# 2_ADSTM32-MCU.net
KiCad netlist of a schematic drawn in Altium Designer
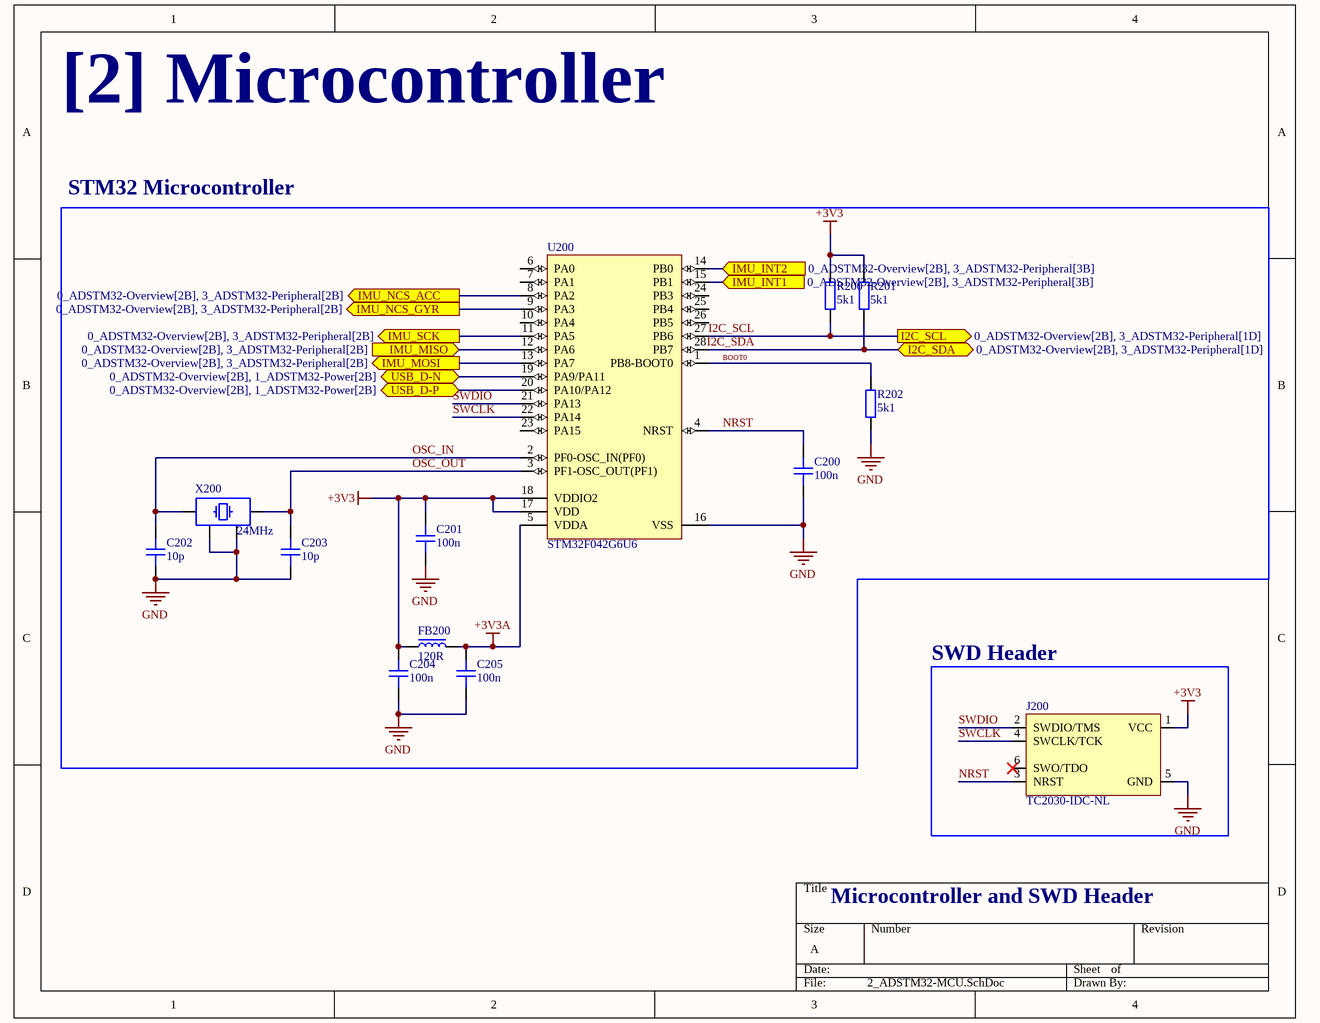
[diagram p0:  2_ADSTM32-MCU.SchDoc]

(export (version "E")
  (design (tool "Eeschema 10.0.6"))
  (components
    (comp (ref "C200")
      (value "100n")
      (footprint "CAP_0603")
      (description "Capaictor SMD 0603 Generic")
      (libsource (lib "Schematic-Lib-KEM") (part "CAP_0603"))
    )
    (comp (ref "C201")
      (value "100n")
      (footprint "CAP_0603")
      (description "Capaictor SMD 0603 Generic")
      (libsource (lib "Schematic-Lib-KEM") (part "CAP_0603"))
    )
    (comp (ref "C202")
      (value "10p")
      (footprint "CAP_0603")
      (description "Capaictor SMD 0603 Generic")
      (libsource (lib "Schematic-Lib-KEM") (part "CAP_0603"))
    )
    (comp (ref "C203")
      (value "10p")
      (footprint "CAP_0603")
      (description "Capaictor SMD 0603 Generic")
      (libsource (lib "Schematic-Lib-KEM") (part "CAP_0603"))
    )
    (comp (ref "C204")
      (value "100n")
      (footprint "CAP_0603")
      (description "Capaictor SMD 0603 Generic")
      (libsource (lib "Schematic-Lib-KEM") (part "CAP_0603"))
    )
    (comp (ref "C205")
      (value "100n")
      (footprint "CAP_0603")
      (description "Capaictor SMD 0603 Generic")
      (libsource (lib "Schematic-Lib-KEM") (part "CAP_0603"))
    )
    (comp (ref "FB200")
      (value "120R")
      (footprint "FB_0603")
      (description "Ferrite Beads BMC-Q 0603 120R 25% Tol. High Current")
      (fields
        (field (name "MANUFACTURER") "Bourns")
        (field (name "MANUFACTURER PART NUMBER") "BMC-Q1JY0120H")
      )
      (libsource (lib "Schematic-Lib-KEM") (part "BMC-Q1JY0120H"))
    )
    (comp (ref "J200")
      (value "TC2030-IDC-NL")
      (footprint "TC2030_NL")
      (description "Tag-Connect No-Solder SWD Debug Connector (No Legs)")
      (libsource (lib "Schematic-Lib-KEM") (part "TC2030-IDC-NL"))
    )
    (comp (ref "R200")
      (value "5k1")
      (footprint "RES_0603")
      (description "Resistor SMD 0603 Generic")
      (libsource (lib "Schematic-Lib-KEM") (part "RES_0603"))
    )
    (comp (ref "R201")
      (value "5k1")
      (footprint "RES_0603")
      (description "Resistor SMD 0603 Generic")
      (libsource (lib "Schematic-Lib-KEM") (part "RES_0603"))
    )
    (comp (ref "R202")
      (value "5k1")
      (footprint "RES_0603")
      (description "Resistor SMD 0603 Generic")
      (libsource (lib "Schematic-Lib-KEM") (part "RES_0603"))
    )
    (comp (ref "U200")
      (value "STM32F042G6U6")
      (footprint "STM-UFQFPN28_V")
      (fields (field (name "MANUFACTURER") "STMicroelectronics"))
      (libsource (lib "Altium Content Vault") (part "MC-ARM-STM32F042-UFQFPN28"))
    )
    (comp (ref "X200")
      (value "24MHz")
      (footprint "XTAL_3225")
      (description "Crystal SMD 24MHz 10PPM 9pF")
      (fields
        (field (name "MANUFACTURER") "Epson")
        (field (name "MANUFACTURER PART NUMBER") "TSX-3225_24.0000MF20G-AC3")
      )
      (libsource (lib "Schematic-Lib-KEM") (part "TSX-3225_24.0000MF20G-AC3"))
    )
  )
  (nets
    (net (code "1") (name "+3V3") (class "Default")
      (node (ref "C201") (pin "2") (pintype "passive"))
      (node (ref "C204") (pin "2") (pintype "passive"))
      (node (ref "FB200") (pin "1") (pintype "passive"))
      (node (ref "J200") (pin "1") (pinfunction "VCC_1") (pintype "passive"))
      (node (ref "R200") (pin "2") (pintype "passive"))
      (node (ref "R201") (pin "2") (pintype "passive"))
      (node (ref "U200") (pin "17") (pinfunction "VDD_17") (pintype "power_in"))
      (node (ref "U200") (pin "18") (pinfunction "VDDIO2_18") (pintype "power_in"))
    )
    (net (code "2") (name "+3V3A") (class "Default")
      (node (ref "C205") (pin "2") (pintype "passive"))
      (node (ref "FB200") (pin "2") (pintype "passive"))
      (node (ref "U200") (pin "5") (pinfunction "VDDA_5") (pintype "power_in"))
    )
    (net (code "3") (name "/BOOT0") (class "Default")
      (node (ref "R202") (pin "2") (pintype "passive"))
      (node (ref "U200") (pin "1") (pinfunction "PB8-BOOT0_1") (pintype "bidirectional"))
    )
    (net (code "4") (name "/I2C_SCL") (class "Default")
      (node (ref "R200") (pin "1") (pintype "passive"))
      (node (ref "U200") (pin "27") (pinfunction "PB6_27") (pintype "bidirectional"))
    )
    (net (code "5") (name "/I2C_SDA") (class "Default")
      (node (ref "R201") (pin "1") (pintype "passive"))
      (node (ref "U200") (pin "28") (pinfunction "PB7_28") (pintype "bidirectional"))
    )
    (net (code "6") (name "/IMU_INT1") (class "Default")
      (node (ref "U200") (pin "15") (pinfunction "PB1_15") (pintype "bidirectional"))
    )
    (net (code "7") (name "/IMU_INT2") (class "Default")
      (node (ref "U200") (pin "14") (pinfunction "PB0_14") (pintype "bidirectional"))
    )
    (net (code "8") (name "/IMU_MISO") (class "Default")
      (node (ref "U200") (pin "12") (pinfunction "PA6_12") (pintype "bidirectional"))
    )
    (net (code "9") (name "/IMU_MOSI") (class "Default")
      (node (ref "U200") (pin "13") (pinfunction "PA7_13") (pintype "bidirectional"))
    )
    (net (code "10") (name "/IMU_NCS_ACC") (class "Default")
      (node (ref "U200") (pin "8") (pinfunction "PA2_8") (pintype "bidirectional"))
    )
    (net (code "11") (name "/IMU_NCS_GYR") (class "Default")
      (node (ref "U200") (pin "9") (pinfunction "PA3_9") (pintype "bidirectional"))
    )
    (net (code "12") (name "/IMU_SCK") (class "Default")
      (node (ref "U200") (pin "11") (pinfunction "PA5_11") (pintype "bidirectional"))
    )
    (net (code "13") (name "/NRST") (class "Default")
      (node (ref "C200") (pin "2") (pintype "passive"))
      (node (ref "J200") (pin "3") (pinfunction "NRST_3") (pintype "passive"))
      (node (ref "U200") (pin "4") (pinfunction "NRST_4") (pintype "bidirectional"))
    )
    (net (code "14") (name "/OSC_IN") (class "Default")
      (node (ref "C202") (pin "2") (pintype "passive"))
      (node (ref "U200") (pin "2") (pinfunction "PF0-OSC_IN(PF0)_2") (pintype "bidirectional"))
      (node (ref "X200") (pin "1") (pinfunction "X1_1") (pintype "passive"))
    )
    (net (code "15") (name "/OSC_OUT") (class "Default")
      (node (ref "C203") (pin "2") (pintype "passive"))
      (node (ref "U200") (pin "3") (pinfunction "PF1-OSC_OUT(PF1)_3") (pintype "bidirectional"))
      (node (ref "X200") (pin "3") (pinfunction "X2_3") (pintype "passive"))
    )
    (net (code "16") (name "/SWCLK") (class "Default")
      (node (ref "J200") (pin "4") (pinfunction "SWCLK/TCK_4") (pintype "passive"))
      (node (ref "U200") (pin "22") (pinfunction "PA14_22") (pintype "bidirectional"))
    )
    (net (code "17") (name "/SWDIO") (class "Default")
      (node (ref "J200") (pin "2") (pinfunction "SWDIO/TMS_2") (pintype "passive"))
      (node (ref "U200") (pin "21") (pinfunction "PA13_21") (pintype "bidirectional"))
    )
    (net (code "18") (name "/USB_D-N") (class "Default")
      (node (ref "U200") (pin "19") (pinfunction "PA9/PA11_19") (pintype "bidirectional"))
    )
    (net (code "19") (name "/USB_D-P") (class "Default")
      (node (ref "U200") (pin "20") (pinfunction "PA10/PA12_20") (pintype "bidirectional"))
    )
    (net (code "20") (name "GND") (class "Default")
      (node (ref "C200") (pin "1") (pintype "passive"))
      (node (ref "C201") (pin "1") (pintype "passive"))
      (node (ref "C202") (pin "1") (pintype "passive"))
      (node (ref "C203") (pin "1") (pintype "passive"))
      (node (ref "C204") (pin "1") (pintype "passive"))
      (node (ref "C205") (pin "1") (pintype "passive"))
      (node (ref "J200") (pin "5") (pinfunction "GND_5") (pintype "power_in"))
      (node (ref "R202") (pin "1") (pintype "passive"))
      (node (ref "U200") (pin "16") (pinfunction "VSS_16") (pintype "power_in"))
      (node (ref "X200") (pin "2") (pinfunction "GND_2") (pintype "power_in"))
      (node (ref "X200") (pin "4") (pinfunction "GND_4") (pintype "power_in"))
    )
    (net (code "21") (name "unconnected-(J200-SWO{slash}TDO-Pad6)") (class "Default")
      (node (ref "J200") (pin "6") (pinfunction "SWO/TDO_6") (pintype "passive+no_connect"))
    )
    (net (code "22") (name "unconnected-(U200-PA0-Pad6)") (class "Default")
      (node (ref "U200") (pin "6") (pinfunction "PA0_6") (pintype "bidirectional"))
    )
    (net (code "23") (name "unconnected-(U200-PA1-Pad7)") (class "Default")
      (node (ref "U200") (pin "7") (pinfunction "PA1_7") (pintype "bidirectional"))
    )
    (net (code "24") (name "unconnected-(U200-PA4-Pad10)") (class "Default")
      (node (ref "U200") (pin "10") (pinfunction "PA4_10") (pintype "bidirectional"))
    )
    (net (code "25") (name "unconnected-(U200-PA15-Pad23)") (class "Default")
      (node (ref "U200") (pin "23") (pinfunction "PA15_23") (pintype "bidirectional"))
    )
    (net (code "26") (name "unconnected-(U200-PB3-Pad24)") (class "Default")
      (node (ref "U200") (pin "24") (pinfunction "PB3_24") (pintype "bidirectional"))
    )
    (net (code "27") (name "unconnected-(U200-PB4-Pad25)") (class "Default")
      (node (ref "U200") (pin "25") (pinfunction "PB4_25") (pintype "bidirectional"))
    )
    (net (code "28") (name "unconnected-(U200-PB5-Pad26)") (class "Default")
      (node (ref "U200") (pin "26") (pinfunction "PB5_26") (pintype "bidirectional"))
    )
  )
)
